# Joysticks.net
KiCad netlist of a schematic drawn in Altium Designer
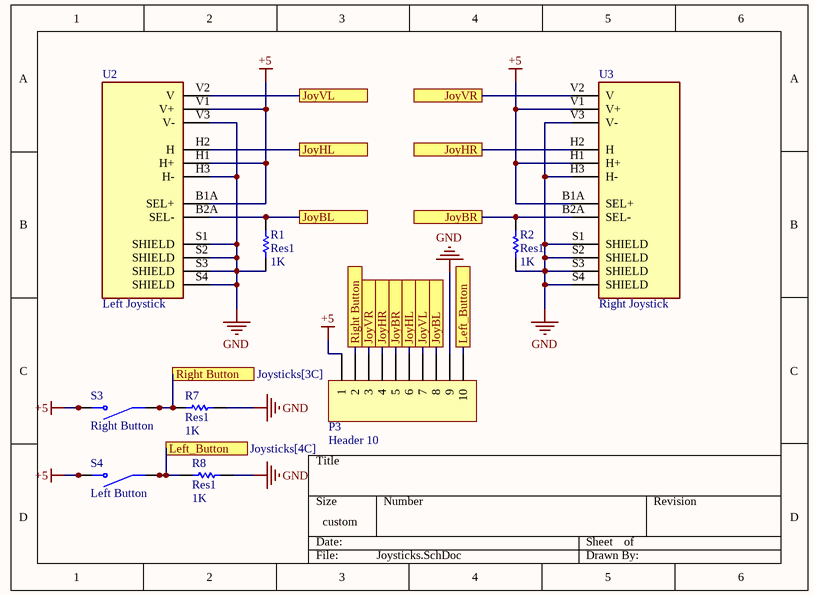
[diagram p0: Joysticks.SchDoc]

(export (version "E")
  (design (tool "Eeschema 10.0.6"))
  (components
    (comp (ref "P3")
      (value "Header 10")
      (footprint "HDR1X10")
      (description "Header, 10-Pin")
      (fields (field (name "PUBLISHER") "Altium Limited"))
      (libsource (lib "Miscellaneous Connectors") (part "Header 10"))
    )
    (comp (ref "R1")
      (value "Res1")
      (footprint "AXIAL-0.3")
      (description "Resistor")
      (fields (field (name "ALTIUM_VALUE") "1K") (field (name "PUBLISHER") "Altium Limited"))
      (libsource (lib "Miscellaneous Devices") (part "Res1"))
    )
    (comp (ref "R2")
      (value "Res1")
      (footprint "AXIAL-0.3")
      (description "Resistor")
      (fields (field (name "ALTIUM_VALUE") "1K") (field (name "PUBLISHER") "Altium Limited"))
      (libsource (lib "Miscellaneous Devices") (part "Res1"))
    )
    (comp (ref "R7")
      (value "Res1")
      (footprint "AXIAL-0.3")
      (description "Resistor")
      (fields (field (name "ALTIUM_VALUE") "1K") (field (name "PUBLISHER") "Altium Limited"))
      (libsource (lib "Miscellaneous Devices") (part "Res1"))
    )
    (comp (ref "R8")
      (value "Res1")
      (footprint "AXIAL-0.3")
      (description "Resistor")
      (fields (field (name "ALTIUM_VALUE") "1K") (field (name "PUBLISHER") "Altium Limited"))
      (libsource (lib "Miscellaneous Devices") (part "Res1"))
    )
    (comp (ref "S3")
      (value "Right Button")
      (footprint "SW_B3F-4055")
      (fields (field (name "MP") "B3F-4055"))
      (libsource (lib "Pushbutton with cap 12x12x4") (part "B3F-4055"))
    )
    (comp (ref "S4")
      (value "Left Button")
      (footprint "SW_B3F-4055")
      (fields (field (name "MP") "B3F-4055"))
      (libsource (lib "Pushbutton with cap 12x12x4") (part "B3F-4055"))
    )
    (comp (ref "U2")
      (value "Left Joystick")
      (footprint "XDCR_COM-09032")
      (description "Thumb Joystick")
      (fields (field (name "MP") "COM-09032"))
      (libsource (lib "Joystick") (part "COM-09032"))
    )
    (comp (ref "U3")
      (value "Right Joystick")
      (footprint "XDCR_COM-09032")
      (description "Thumb Joystick")
      (fields (field (name "MP") "COM-09032"))
      (libsource (lib "") (part "COM-09032_1"))
    )
  )
  (nets
    (net (code "1") (name "+5") (class "Default")
      (node (ref "P3") (pin "1") (pinfunction "1_1") (pintype "passive"))
      (node (ref "S3") (pin "3") (pinfunction "NO_3") (pintype "passive"))
      (node (ref "S3") (pin "4") (pinfunction "NO_4") (pintype "passive"))
      (node (ref "S4") (pin "3") (pinfunction "NO_3") (pintype "passive"))
      (node (ref "S4") (pin "4") (pinfunction "NO_4") (pintype "passive"))
      (node (ref "U2") (pin "B1A") (pinfunction "SEL+_B1A") (pintype "passive"))
      (node (ref "U2") (pin "H1") (pinfunction "H+_H1") (pintype "passive"))
      (node (ref "U2") (pin "V1") (pinfunction "V+_V1") (pintype "passive"))
      (node (ref "U3") (pin "B1A") (pinfunction "SEL+_B1A") (pintype "passive"))
      (node (ref "U3") (pin "H1") (pinfunction "H+_H1") (pintype "passive"))
      (node (ref "U3") (pin "V1") (pinfunction "V+_V1") (pintype "passive"))
    )
    (net (code "2") (name "/JoyBL") (class "Default")
      (node (ref "P3") (pin "8") (pinfunction "8_8") (pintype "passive"))
      (node (ref "R1") (pin "2") (pinfunction "2_2") (pintype "passive"))
      (node (ref "U2") (pin "B2A") (pinfunction "SEL-_B2A") (pintype "passive"))
    )
    (net (code "3") (name "/JoyBR") (class "Default")
      (node (ref "P3") (pin "5") (pinfunction "5_5") (pintype "passive"))
      (node (ref "R2") (pin "2") (pinfunction "2_2") (pintype "passive"))
      (node (ref "U3") (pin "B2A") (pinfunction "SEL-_B2A") (pintype "passive"))
    )
    (net (code "4") (name "/JoyHL") (class "Default")
      (node (ref "P3") (pin "6") (pinfunction "6_6") (pintype "passive"))
      (node (ref "U2") (pin "H2") (pinfunction "H_H2") (pintype "passive"))
    )
    (net (code "5") (name "/JoyHR") (class "Default")
      (node (ref "P3") (pin "4") (pinfunction "4_4") (pintype "passive"))
      (node (ref "U3") (pin "H2") (pinfunction "H_H2") (pintype "passive"))
    )
    (net (code "6") (name "/JoyVL") (class "Default")
      (node (ref "P3") (pin "7") (pinfunction "7_7") (pintype "passive"))
      (node (ref "U2") (pin "V2") (pinfunction "V_V2") (pintype "passive"))
    )
    (net (code "7") (name "/JoyVR") (class "Default")
      (node (ref "P3") (pin "3") (pinfunction "3_3") (pintype "passive"))
      (node (ref "U3") (pin "V2") (pinfunction "V_V2") (pintype "passive"))
    )
    (net (code "8") (name "/Left_Button") (class "Default")
      (node (ref "P3") (pin "10") (pinfunction "10_10") (pintype "passive"))
      (node (ref "R8") (pin "2") (pinfunction "2_2") (pintype "passive"))
      (node (ref "S4") (pin "1") (pinfunction "COM_1") (pintype "passive"))
      (node (ref "S4") (pin "2") (pinfunction "COM_2") (pintype "passive"))
    )
    (net (code "9") (name "/Right Button") (class "Default")
      (node (ref "P3") (pin "2") (pinfunction "2_2") (pintype "passive"))
      (node (ref "R7") (pin "2") (pinfunction "2_2") (pintype "passive"))
      (node (ref "S3") (pin "1") (pinfunction "COM_1") (pintype "passive"))
      (node (ref "S3") (pin "2") (pinfunction "COM_2") (pintype "passive"))
    )
    (net (code "10") (name "GND") (class "Default")
      (node (ref "P3") (pin "9") (pinfunction "9_9") (pintype "passive"))
      (node (ref "R1") (pin "1") (pinfunction "1_1") (pintype "passive"))
      (node (ref "R2") (pin "1") (pinfunction "1_1") (pintype "passive"))
      (node (ref "R7") (pin "1") (pinfunction "1_1") (pintype "passive"))
      (node (ref "R8") (pin "1") (pinfunction "1_1") (pintype "passive"))
      (node (ref "U2") (pin "H3") (pinfunction "H-_H3") (pintype "passive"))
      (node (ref "U2") (pin "S1") (pinfunction "SHIELD_S1") (pintype "passive"))
      (node (ref "U2") (pin "S2") (pinfunction "SHIELD_S2") (pintype "passive"))
      (node (ref "U2") (pin "S3") (pinfunction "SHIELD_S3") (pintype "passive"))
      (node (ref "U2") (pin "S4") (pinfunction "SHIELD_S4") (pintype "passive"))
      (node (ref "U2") (pin "V3") (pinfunction "V-_V3") (pintype "passive"))
      (node (ref "U3") (pin "H3") (pinfunction "H-_H3") (pintype "passive"))
      (node (ref "U3") (pin "S1") (pinfunction "SHIELD_S1") (pintype "passive"))
      (node (ref "U3") (pin "S2") (pinfunction "SHIELD_S2") (pintype "passive"))
      (node (ref "U3") (pin "S3") (pinfunction "SHIELD_S3") (pintype "passive"))
      (node (ref "U3") (pin "S4") (pinfunction "SHIELD_S4") (pintype "passive"))
      (node (ref "U3") (pin "V3") (pinfunction "V-_V3") (pintype "passive"))
    )
  )
)
